# EFR32MG22_module.net
KiCad netlist of a schematic drawn in EAGLE
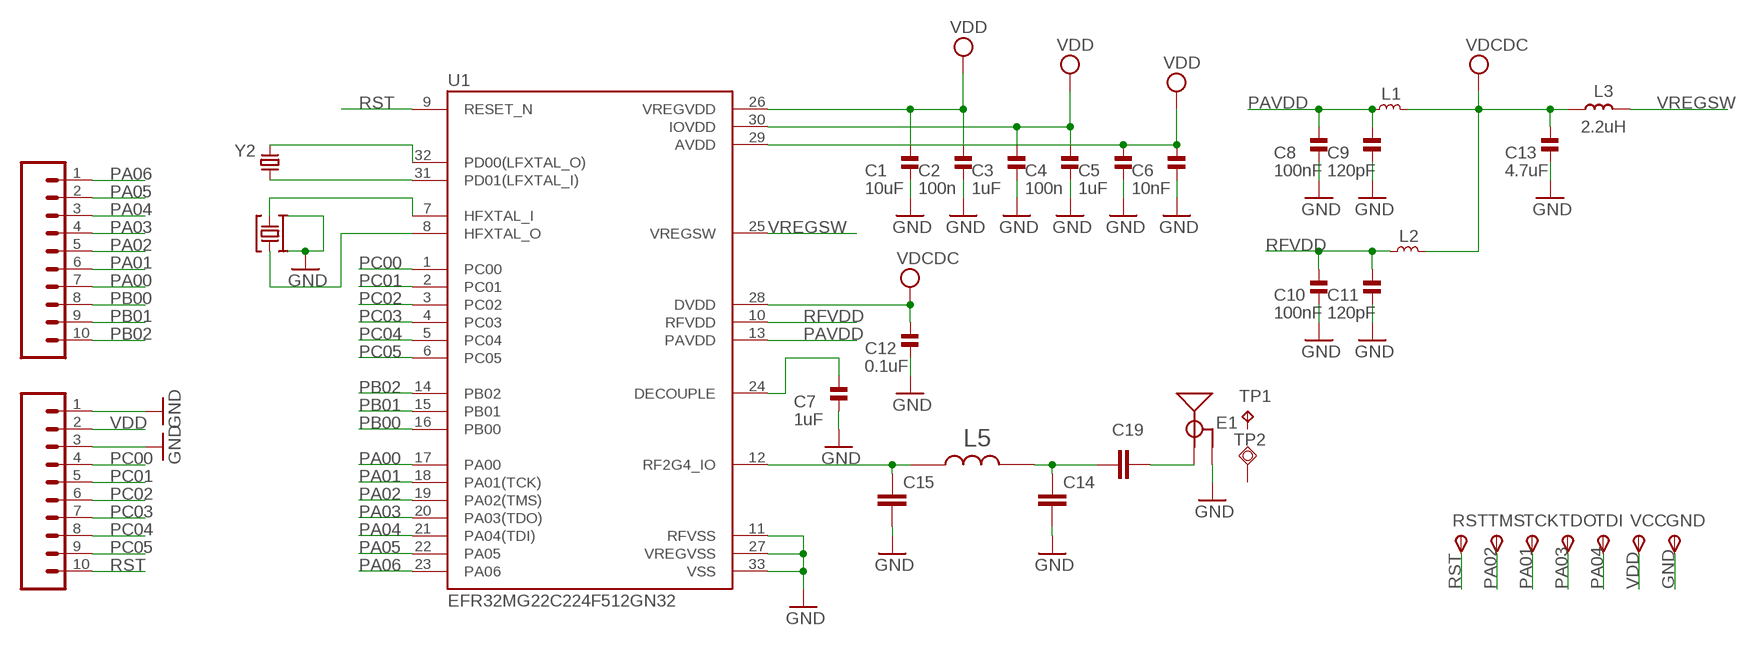
[diagram p0: schematic, sheet 1]

(export (version "E")
  (design (tool "Eeschema 10.0.6"))
  (components
    (comp (ref "C1")
      (value "10uF")
      (footprint "eagle-import:_PKG_C_0805")
      (libsource (lib "eagle-import") (part "CAP-0805"))
    )
    (comp (ref "C2")
      (value "100n")
      (footprint "eagle-import:_PKG_C_0402")
      (libsource (lib "eagle-import") (part "CAP-0402"))
    )
    (comp (ref "C3")
      (value "1uF")
      (footprint "eagle-import:_PKG_C_0402")
      (libsource (lib "eagle-import") (part "CAP-0402"))
    )
    (comp (ref "C4")
      (value "100n")
      (footprint "eagle-import:_PKG_C_0402")
      (libsource (lib "eagle-import") (part "CAP-0402"))
    )
    (comp (ref "C5")
      (value "1uF")
      (footprint "eagle-import:_PKG_C_0402")
      (libsource (lib "eagle-import") (part "CAP-0402"))
    )
    (comp (ref "C6")
      (value "10nF")
      (footprint "eagle-import:_PKG_C_0402")
      (libsource (lib "eagle-import") (part "CAP-0402"))
    )
    (comp (ref "C7")
      (value "1uF")
      (footprint "eagle-import:_PKG_C_0402")
      (libsource (lib "eagle-import") (part "CAP-0402"))
    )
    (comp (ref "C8")
      (value "100nF")
      (footprint "eagle-import:_PKG_C_0402")
      (libsource (lib "eagle-import") (part "CAP-0402"))
    )
    (comp (ref "C9")
      (value "120pF")
      (footprint "eagle-import:_PKG_C_0402")
      (libsource (lib "eagle-import") (part "CAP-0402"))
    )
    (comp (ref "C10")
      (value "100nF")
      (footprint "eagle-import:_PKG_C_0402")
      (libsource (lib "eagle-import") (part "CAP-0402"))
    )
    (comp (ref "C11")
      (value "120pF")
      (footprint "eagle-import:_PKG_C_0402")
      (libsource (lib "eagle-import") (part "CAP-0402"))
    )
    (comp (ref "C12")
      (value "0.1uF")
      (footprint "eagle-import:_PKG_C_0402")
      (libsource (lib "eagle-import") (part "CAP-0402"))
    )
    (comp (ref "C13")
      (value "4.7uF")
      (footprint "eagle-import:_PKG_C_0402")
      (libsource (lib "eagle-import") (part "CAP-0402"))
    )
    (comp (ref "C14")
      (value "1.3pF")
      (footprint "eagle-import:CAPC1005X40N")
      (fields (field (name "MF") "Yageo") (field (name "MP") "RC0402FR-073M6L"))
      (libsource (lib "eagle-import") (part "CAP0402"))
    )
    (comp (ref "C15")
      (value "1.2pF")
      (footprint "eagle-import:CAPC1005X40N")
      (fields (field (name "MF") "Yageo") (field (name "MP") "RC0402FR-073M6L"))
      (libsource (lib "eagle-import") (part "CAP0402"))
    )
    (comp (ref "C19")
      (value "18pF")
      (footprint "eagle-import:CAPC1005X40N")
      (fields (field (name "MF") "Yageo") (field (name "MP") "RC0402FR-073M6L"))
      (libsource (lib "eagle-import") (part "CAP0402"))
    )
    (comp (ref "E1")
      (value "ANTENNA-GROUNDEDTRACE-15.2MM")
      (footprint "eagle-import:TRACE_ANTENNA_2.4GHZ_15.2MM")
      (libsource (lib "eagle-import") (part "ANTENNA-GROUNDEDTRACE-15.2MM"))
    )
    (comp (ref "GND")
      (value "TPSTP11R")
      (footprint "eagle-import:TP11R")
      (libsource (lib "eagle-import") (part "TPSTP11R"))
    )
    (comp (ref "J1")
      (value "CONN_061.27MM")
      (footprint "eagle-import:1X06_1.27MM")
      (libsource (lib "eagle-import") (part "CONN_061.27MM"))
    )
    (comp (ref "J2")
      (value "CONN_061.27MM")
      (footprint "eagle-import:1X06_1.27MM")
      (libsource (lib "eagle-import") (part "CONN_061.27MM"))
    )
    (comp (ref "L1")
      (value "BLM18AG102SN1")
      (footprint "eagle-import:_PKG_L_0603")
      (libsource (lib "eagle-import") (part "INDUCTOR-0603"))
    )
    (comp (ref "L2")
      (value "BLM18AG102SN1")
      (footprint "eagle-import:_PKG_L_0603")
      (libsource (lib "eagle-import") (part "INDUCTOR-0603"))
    )
    (comp (ref "L3")
      (value "2.2uH")
      (footprint "eagle-import:INDC2520X120N")
      (libsource (lib "eagle-import") (part "LCHIP-1008(2520-METRIC)_"))
    )
    (comp (ref "L5")
      (value "2.6nH")
      (footprint "eagle-import:INDC1005X40N")
      (fields (field (name "MF") "Yageo") (field (name "MP") "RC0402FR-073M6L"))
      (libsource (lib "eagle-import") (part "IND0402IND0402"))
    )
    (comp (ref "RST")
      (value "TPSTP11R")
      (footprint "eagle-import:TP11R")
      (libsource (lib "eagle-import") (part "TPSTP11R"))
    )
    (comp (ref "TCK")
      (value "TPSTP11R")
      (footprint "eagle-import:TP11R")
      (libsource (lib "eagle-import") (part "TPSTP11R"))
    )
    (comp (ref "TDI")
      (value "TPSTP11R")
      (footprint "eagle-import:TP11R")
      (libsource (lib "eagle-import") (part "TPSTP11R"))
    )
    (comp (ref "TDO")
      (value "TPSTP11R")
      (footprint "eagle-import:TP11R")
      (libsource (lib "eagle-import") (part "TPSTP11R"))
    )
    (comp (ref "TMS")
      (value "TPSTP11R")
      (footprint "eagle-import:TP11R")
      (libsource (lib "eagle-import") (part "TPSTP11R"))
    )
    (comp (ref "TP1")
      (value "TPTP06SQ")
      (footprint "eagle-import:TP05SQ")
      (libsource (lib "eagle-import") (part "TPTP06SQ"))
    )
    (comp (ref "TP2")
      (value "TPSQTP15SQ")
      (footprint "eagle-import:TP15SQ")
      (libsource (lib "eagle-import") (part "TPSQTP15SQ"))
    )
    (comp (ref "U1")
      (value "EFR32MG22C224F512GN32")
      (footprint "eagle-import:QFN50P500X500X90-33N")
      (fields (field (name "MF") "Silicon Labs") (field (name "MP") "EFR32MG14P732F256GM32-B"))
      (libsource (lib "eagle-import") (part "EFR32MG22C224F512GN32"))
    )
    (comp (ref "VCC")
      (value "TPSTP11R")
      (footprint "eagle-import:TP11R")
      (libsource (lib "eagle-import") (part "TPSTP11R"))
    )
    (comp (ref "Y1")
      (value "38.4MHZ")
      (footprint "eagle-import:XTAL-4P-2016")
      (fields (field (name "DIGIKEY_PART") "1253-2042-1-ND") (field (name "MFG_PART") "CX2016DB48000C0FPLC1"))
      (libsource (lib "eagle-import") (part "48.000MHZ_CX2016DB48000C0FPLC1"))
    )
    (comp (ref "Y2")
      (value "32.768KHz")
      (footprint "eagle-import:XTAL-2P-3215")
      (fields (field (name "LCSC_PART") "C32346") (field (name "MFG_PART") "Q13FC1350000400"))
      (libsource (lib "eagle-import") (part "32.768KHZ_Q13FC1350000400"))
    )
  )
  (nets
    (net (code "1") (name "/PA00") (class "Default")
      (node (ref "J1") (pin "7") (pinfunction "7_7") (pintype "passive"))
      (node (ref "U1") (pin "17") (pinfunction "PA00_17") (pintype "bidirectional"))
    )
    (net (code "2") (name "/PA01") (class "Default")
      (node (ref "J1") (pin "6") (pinfunction "6_6") (pintype "passive"))
      (node (ref "TCK") (pin "TP") (pinfunction "PP_TP") (pintype "input"))
      (node (ref "U1") (pin "18") (pinfunction "PA01(TCK)_18") (pintype "bidirectional"))
    )
    (net (code "3") (name "/PA02") (class "Default")
      (node (ref "J1") (pin "5") (pinfunction "5_5") (pintype "passive"))
      (node (ref "TMS") (pin "TP") (pinfunction "PP_TP") (pintype "input"))
      (node (ref "U1") (pin "19") (pinfunction "PA02(TMS)_19") (pintype "bidirectional"))
    )
    (net (code "4") (name "/PA03") (class "Default")
      (node (ref "J1") (pin "4") (pinfunction "4_4") (pintype "passive"))
      (node (ref "TDO") (pin "TP") (pinfunction "PP_TP") (pintype "input"))
      (node (ref "U1") (pin "20") (pinfunction "PA03(TDO)_20") (pintype "bidirectional"))
    )
    (net (code "5") (name "/PA04") (class "Default")
      (node (ref "J1") (pin "3") (pinfunction "3_3") (pintype "passive"))
      (node (ref "TDI") (pin "TP") (pinfunction "PP_TP") (pintype "input"))
      (node (ref "U1") (pin "21") (pinfunction "PA04(TDI)_21") (pintype "bidirectional"))
    )
    (net (code "6") (name "/PA05") (class "Default")
      (node (ref "J1") (pin "2") (pinfunction "2_2") (pintype "passive"))
      (node (ref "U1") (pin "22") (pinfunction "PA05_22") (pintype "bidirectional"))
    )
    (net (code "7") (name "/PA06") (class "Default")
      (node (ref "J1") (pin "1") (pinfunction "1_1") (pintype "passive"))
      (node (ref "U1") (pin "23") (pinfunction "PA06_23") (pintype "bidirectional"))
    )
    (net (code "8") (name "/PAVDD") (class "Default")
      (node (ref "C8") (pin "1") (pinfunction "1_1") (pintype "passive"))
      (node (ref "C9") (pin "1") (pinfunction "1_1") (pintype "passive"))
      (node (ref "L1") (pin "1") (pinfunction "1_1") (pintype "passive"))
      (node (ref "U1") (pin "13") (pinfunction "PAVDD_13") (pintype "power_in"))
    )
    (net (code "9") (name "/PB00") (class "Default")
      (node (ref "J1") (pin "8") (pinfunction "8_8") (pintype "passive"))
      (node (ref "U1") (pin "16") (pinfunction "PB00_16") (pintype "bidirectional"))
    )
    (net (code "10") (name "/PB01") (class "Default")
      (node (ref "J1") (pin "9") (pinfunction "9_9") (pintype "passive"))
      (node (ref "U1") (pin "15") (pinfunction "PB01_15") (pintype "bidirectional"))
    )
    (net (code "11") (name "/PB02") (class "Default")
      (node (ref "J1") (pin "10") (pinfunction "10_10") (pintype "passive"))
      (node (ref "U1") (pin "14") (pinfunction "PB02_14") (pintype "power_in"))
    )
    (net (code "12") (name "/PC00") (class "Default")
      (node (ref "J2") (pin "4") (pinfunction "4_4") (pintype "passive"))
      (node (ref "U1") (pin "1") (pinfunction "PC00_1") (pintype "bidirectional"))
    )
    (net (code "13") (name "/PC01") (class "Default")
      (node (ref "J2") (pin "5") (pinfunction "5_5") (pintype "passive"))
      (node (ref "U1") (pin "2") (pinfunction "PC01_2") (pintype "bidirectional"))
    )
    (net (code "14") (name "/PC02") (class "Default")
      (node (ref "J2") (pin "6") (pinfunction "6_6") (pintype "passive"))
      (node (ref "U1") (pin "3") (pinfunction "PC02_3") (pintype "bidirectional"))
    )
    (net (code "15") (name "/PC03") (class "Default")
      (node (ref "J2") (pin "7") (pinfunction "7_7") (pintype "passive"))
      (node (ref "U1") (pin "4") (pinfunction "PC03_4") (pintype "bidirectional"))
    )
    (net (code "16") (name "/PC04") (class "Default")
      (node (ref "J2") (pin "8") (pinfunction "8_8") (pintype "passive"))
      (node (ref "U1") (pin "5") (pinfunction "PC04_5") (pintype "bidirectional"))
    )
    (net (code "17") (name "/PC05") (class "Default")
      (node (ref "J2") (pin "9") (pinfunction "9_9") (pintype "passive"))
      (node (ref "U1") (pin "6") (pinfunction "PC05_6") (pintype "bidirectional"))
    )
    (net (code "18") (name "/RFVDD") (class "Default")
      (node (ref "C10") (pin "1") (pinfunction "1_1") (pintype "passive"))
      (node (ref "C11") (pin "1") (pinfunction "1_1") (pintype "passive"))
      (node (ref "L2") (pin "1") (pinfunction "1_1") (pintype "passive"))
      (node (ref "U1") (pin "10") (pinfunction "RFVDD_10") (pintype "power_in"))
    )
    (net (code "19") (name "/RST") (class "Default")
      (node (ref "J2") (pin "10") (pinfunction "10_10") (pintype "passive"))
      (node (ref "RST") (pin "TP") (pinfunction "PP_TP") (pintype "input"))
      (node (ref "U1") (pin "9") (pinfunction "RESET_N_9") (pintype "input"))
    )
    (net (code "20") (name "/VREGSW") (class "Default")
      (node (ref "L3") (pin "2") (pinfunction "2_2") (pintype "passive"))
      (node (ref "U1") (pin "25") (pinfunction "VREGSW_25") (pintype "bidirectional"))
    )
    (net (code "21") (name "GND") (class "Default")
      (node (ref "C1") (pin "2") (pinfunction "2_2") (pintype "passive"))
      (node (ref "C10") (pin "2") (pinfunction "2_2") (pintype "passive"))
      (node (ref "C11") (pin "2") (pinfunction "2_2") (pintype "passive"))
      (node (ref "C12") (pin "2") (pinfunction "2_2") (pintype "passive"))
      (node (ref "C13") (pin "2") (pinfunction "2_2") (pintype "passive"))
      (node (ref "C14") (pin "2") (pinfunction "2_2") (pintype "passive"))
      (node (ref "C15") (pin "2") (pinfunction "2_2") (pintype "passive"))
      (node (ref "C2") (pin "2") (pinfunction "2_2") (pintype "passive"))
      (node (ref "C3") (pin "2") (pinfunction "2_2") (pintype "passive"))
      (node (ref "C4") (pin "2") (pinfunction "2_2") (pintype "passive"))
      (node (ref "C5") (pin "2") (pinfunction "2_2") (pintype "passive"))
      (node (ref "C6") (pin "2") (pinfunction "2_2") (pintype "passive"))
      (node (ref "C7") (pin "2") (pinfunction "2_2") (pintype "passive"))
      (node (ref "C8") (pin "2") (pinfunction "2_2") (pintype "passive"))
      (node (ref "C9") (pin "2") (pinfunction "2_2") (pintype "passive"))
      (node (ref "E1") (pin "GND") (pinfunction "GND_GND") (pintype "bidirectional"))
      (node (ref "GND") (pin "TP") (pinfunction "PP_TP") (pintype "input"))
      (node (ref "J2") (pin "1") (pinfunction "1_1") (pintype "passive"))
      (node (ref "J2") (pin "3") (pinfunction "3_3") (pintype "passive"))
      (node (ref "U1") (pin "11") (pinfunction "RFVSS_11") (pintype "power_in"))
      (node (ref "U1") (pin "27") (pinfunction "VREGVSS_27") (pintype "power_in"))
      (node (ref "U1") (pin "33") (pinfunction "VSS_33") (pintype "power_in"))
      (node (ref "Y1") (pin "2") (pinfunction "2_2") (pintype "bidirectional"))
      (node (ref "Y1") (pin "4") (pinfunction "4_4") (pintype "bidirectional"))
    )
    (net (code "22") (name "Net-(C14-Pad1)") (class "Default")
      (node (ref "C14") (pin "1") (pinfunction "1_1") (pintype "passive"))
      (node (ref "C19") (pin "1") (pinfunction "1_1") (pintype "passive"))
      (node (ref "L5") (pin "2") (pinfunction "2_2") (pintype "passive"))
    )
    (net (code "23") (name "Net-(E1-SIGNAL)") (class "Default")
      (node (ref "C19") (pin "2") (pinfunction "2_2") (pintype "passive"))
      (node (ref "E1") (pin "ANT") (pinfunction "SIGNAL_ANT") (pintype "bidirectional"))
    )
    (net (code "24") (name "Net-(U1-DECOUPLE)") (class "Default")
      (node (ref "C7") (pin "1") (pinfunction "1_1") (pintype "passive"))
      (node (ref "U1") (pin "24") (pinfunction "DECOUPLE_24") (pintype "output"))
    )
    (net (code "25") (name "Net-(U1-HFXTAL_I)") (class "Default")
      (node (ref "U1") (pin "7") (pinfunction "HFXTAL_I_7") (pintype "input"))
      (node (ref "Y1") (pin "3") (pinfunction "3_3") (pintype "passive"))
    )
    (net (code "26") (name "Net-(U1-HFXTAL_O)") (class "Default")
      (node (ref "U1") (pin "8") (pinfunction "HFXTAL_O_8") (pintype "output"))
      (node (ref "Y1") (pin "1") (pinfunction "1_1") (pintype "passive"))
    )
    (net (code "27") (name "Net-(U1-PD00(LFXTAL_O))") (class "Default")
      (node (ref "U1") (pin "32") (pinfunction "PD00(LFXTAL_O)_32") (pintype "bidirectional"))
      (node (ref "Y2") (pin "1") (pinfunction "1_1") (pintype "passive"))
    )
    (net (code "28") (name "Net-(U1-PD01(LFXTAL_I))") (class "Default")
      (node (ref "U1") (pin "31") (pinfunction "PD01(LFXTAL_I)_31") (pintype "bidirectional"))
      (node (ref "Y2") (pin "2") (pinfunction "2_2") (pintype "passive"))
    )
    (net (code "29") (name "Net-(U1-RF2G4_IO)") (class "Default")
      (node (ref "C15") (pin "1") (pinfunction "1_1") (pintype "passive"))
      (node (ref "L5") (pin "1") (pinfunction "1_1") (pintype "passive"))
      (node (ref "U1") (pin "12") (pinfunction "RF2G4_IO_12") (pintype "bidirectional"))
    )
    (net (code "30") (name "VDCDC") (class "Default")
      (node (ref "C12") (pin "1") (pinfunction "1_1") (pintype "passive"))
      (node (ref "C13") (pin "1") (pinfunction "1_1") (pintype "passive"))
      (node (ref "L1") (pin "2") (pinfunction "2_2") (pintype "passive"))
      (node (ref "L2") (pin "2") (pinfunction "2_2") (pintype "passive"))
      (node (ref "L3") (pin "1") (pinfunction "1_1") (pintype "passive"))
      (node (ref "U1") (pin "28") (pinfunction "DVDD_28") (pintype "power_in"))
    )
    (net (code "31") (name "VDD") (class "Default")
      (node (ref "C1") (pin "1") (pinfunction "1_1") (pintype "passive"))
      (node (ref "C2") (pin "1") (pinfunction "1_1") (pintype "passive"))
      (node (ref "C3") (pin "1") (pinfunction "1_1") (pintype "passive"))
      (node (ref "C4") (pin "1") (pinfunction "1_1") (pintype "passive"))
      (node (ref "C5") (pin "1") (pinfunction "1_1") (pintype "passive"))
      (node (ref "C6") (pin "1") (pinfunction "1_1") (pintype "passive"))
      (node (ref "J2") (pin "2") (pinfunction "2_2") (pintype "passive"))
      (node (ref "U1") (pin "26") (pinfunction "VREGVDD_26") (pintype "power_in"))
      (node (ref "U1") (pin "29") (pinfunction "AVDD_29") (pintype "power_in"))
      (node (ref "U1") (pin "30") (pinfunction "IOVDD_30") (pintype "power_in"))
      (node (ref "VCC") (pin "TP") (pinfunction "PP_TP") (pintype "input"))
    )
    (net (code "32") (name "unconnected-(TP1-PadTP)") (class "Default")
      (node (ref "TP1") (pin "TP") (pinfunction "TP_TP") (pintype "input"))
    )
    (net (code "33") (name "unconnected-(TP2-PadTP)") (class "Default")
      (node (ref "TP2") (pin "TP") (pinfunction "TP_TP") (pintype "input"))
    )
  )
)
